# Input_v1_0.net
KiCad netlist of a schematic drawn in EAGLE
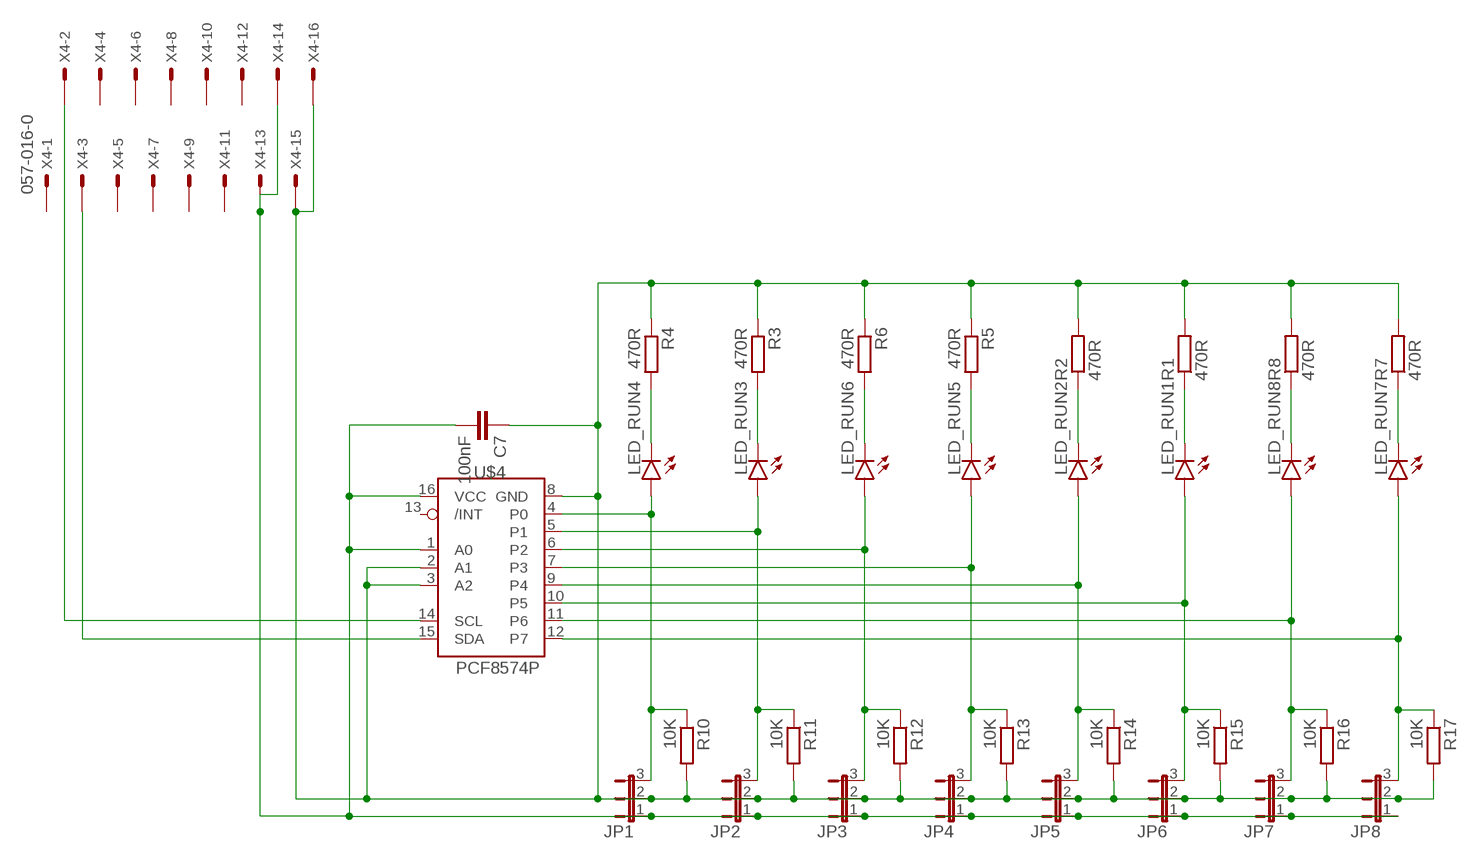
[diagram p0: schematic, sheet 1]

(export (version "E")
  (design (tool "Eeschema 10.0.6"))
  (components
    (comp (ref "C7")
      (value "100nF")
      (footprint "eagle-import:C025-024X044")
      (libsource (lib "eagle-import") (part "C-EU025-024X044"))
    )
    (comp (ref "JP1")
      (value "JP2E")
      (footprint "eagle-import:JP2")
      (libsource (lib "eagle-import") (part "JP2E"))
    )
    (comp (ref "JP2")
      (value "JP2E")
      (footprint "eagle-import:JP2")
      (libsource (lib "eagle-import") (part "JP2E"))
    )
    (comp (ref "JP3")
      (value "JP2E")
      (footprint "eagle-import:JP2")
      (libsource (lib "eagle-import") (part "JP2E"))
    )
    (comp (ref "JP4")
      (value "JP2E")
      (footprint "eagle-import:JP2")
      (libsource (lib "eagle-import") (part "JP2E"))
    )
    (comp (ref "JP5")
      (value "JP2E")
      (footprint "eagle-import:JP2")
      (libsource (lib "eagle-import") (part "JP2E"))
    )
    (comp (ref "JP6")
      (value "JP2E")
      (footprint "eagle-import:JP2")
      (libsource (lib "eagle-import") (part "JP2E"))
    )
    (comp (ref "JP7")
      (value "JP2E")
      (footprint "eagle-import:JP2")
      (libsource (lib "eagle-import") (part "JP2E"))
    )
    (comp (ref "JP8")
      (value "JP2E")
      (footprint "eagle-import:JP2")
      (libsource (lib "eagle-import") (part "JP2E"))
    )
    (comp (ref "LED_RUN1")
      (value "LED3MM")
      (footprint "eagle-import:LED3MM")
      (libsource (lib "eagle-import") (part "LED3MM"))
    )
    (comp (ref "LED_RUN2")
      (value "LED3MM")
      (footprint "eagle-import:LED3MM")
      (libsource (lib "eagle-import") (part "LED3MM"))
    )
    (comp (ref "LED_RUN3")
      (value "LED3MM")
      (footprint "eagle-import:LED3MM")
      (libsource (lib "eagle-import") (part "LED3MM"))
    )
    (comp (ref "LED_RUN4")
      (value "LED3MM")
      (footprint "eagle-import:LED3MM")
      (libsource (lib "eagle-import") (part "LED3MM"))
    )
    (comp (ref "LED_RUN5")
      (value "LED3MM")
      (footprint "eagle-import:LED3MM")
      (libsource (lib "eagle-import") (part "LED3MM"))
    )
    (comp (ref "LED_RUN6")
      (value "LED3MM")
      (footprint "eagle-import:LED3MM")
      (libsource (lib "eagle-import") (part "LED3MM"))
    )
    (comp (ref "LED_RUN7")
      (value "LED3MM")
      (footprint "eagle-import:LED3MM")
      (libsource (lib "eagle-import") (part "LED3MM"))
    )
    (comp (ref "LED_RUN8")
      (value "LED3MM")
      (footprint "eagle-import:LED3MM")
      (libsource (lib "eagle-import") (part "LED3MM"))
    )
    (comp (ref "R1")
      (value "470R")
      (footprint "eagle-import:0309_10")
      (libsource (lib "eagle-import") (part "R-EU_0309/10"))
    )
    (comp (ref "R2")
      (value "470R")
      (footprint "eagle-import:0309_10")
      (libsource (lib "eagle-import") (part "R-EU_0309/10"))
    )
    (comp (ref "R3")
      (value "470R")
      (footprint "eagle-import:0309_10")
      (libsource (lib "eagle-import") (part "R-EU_0309/10"))
    )
    (comp (ref "R4")
      (value "470R")
      (footprint "eagle-import:0309_10")
      (libsource (lib "eagle-import") (part "R-EU_0309/10"))
    )
    (comp (ref "R5")
      (value "470R")
      (footprint "eagle-import:0309_10")
      (libsource (lib "eagle-import") (part "R-EU_0309/10"))
    )
    (comp (ref "R6")
      (value "470R")
      (footprint "eagle-import:0309_10")
      (libsource (lib "eagle-import") (part "R-EU_0309/10"))
    )
    (comp (ref "R7")
      (value "470R")
      (footprint "eagle-import:0309_10")
      (libsource (lib "eagle-import") (part "R-EU_0309/10"))
    )
    (comp (ref "R8")
      (value "470R")
      (footprint "eagle-import:0309_10")
      (libsource (lib "eagle-import") (part "R-EU_0309/10"))
    )
    (comp (ref "R10")
      (value "10K")
      (footprint "eagle-import:0309_10")
      (libsource (lib "eagle-import") (part "R-EU_0309/10"))
    )
    (comp (ref "R11")
      (value "10K")
      (footprint "eagle-import:0309_10")
      (libsource (lib "eagle-import") (part "R-EU_0309/10"))
    )
    (comp (ref "R12")
      (value "10K")
      (footprint "eagle-import:0309_10")
      (libsource (lib "eagle-import") (part "R-EU_0309/10"))
    )
    (comp (ref "R13")
      (value "10K")
      (footprint "eagle-import:0309_10")
      (libsource (lib "eagle-import") (part "R-EU_0309/10"))
    )
    (comp (ref "R14")
      (value "10K")
      (footprint "eagle-import:0309_10")
      (libsource (lib "eagle-import") (part "R-EU_0309/10"))
    )
    (comp (ref "R15")
      (value "10K")
      (footprint "eagle-import:0309_10")
      (libsource (lib "eagle-import") (part "R-EU_0309/10"))
    )
    (comp (ref "R16")
      (value "10K")
      (footprint "eagle-import:0309_10")
      (libsource (lib "eagle-import") (part "R-EU_0309/10"))
    )
    (comp (ref "R17")
      (value "10K")
      (footprint "eagle-import:0309_10")
      (libsource (lib "eagle-import") (part "R-EU_0309/10"))
    )
    (comp (ref "U$4")
      (value "PCF8574P")
      (footprint "eagle-import:DIL16")
      (libsource (lib "eagle-import") (part "PCF8574P"))
    )
    (comp (ref "X4")
      (value "057-016-0")
      (footprint "eagle-import:057-016-0")
      (libsource (lib "eagle-import") (part "057-016-0"))
    )
  )
  (nets
    (net (code "1") (name "Net-(LED_RUN1-C)") (class "Default")
      (node (ref "LED_RUN1") (pin "K") (pinfunction "C_K") (pintype "passive"))
      (node (ref "R1") (pin "1") (pinfunction "1_1") (pintype "passive"))
    )
    (net (code "2") (name "Net-(LED_RUN2-C)") (class "Default")
      (node (ref "LED_RUN2") (pin "K") (pinfunction "C_K") (pintype "passive"))
      (node (ref "R2") (pin "1") (pinfunction "1_1") (pintype "passive"))
    )
    (net (code "3") (name "Net-(LED_RUN3-C)") (class "Default")
      (node (ref "LED_RUN3") (pin "K") (pinfunction "C_K") (pintype "passive"))
      (node (ref "R3") (pin "2") (pinfunction "2_2") (pintype "passive"))
    )
    (net (code "4") (name "Net-(LED_RUN4-C)") (class "Default")
      (node (ref "LED_RUN4") (pin "K") (pinfunction "C_K") (pintype "passive"))
      (node (ref "R4") (pin "2") (pinfunction "2_2") (pintype "passive"))
    )
    (net (code "5") (name "Net-(LED_RUN5-C)") (class "Default")
      (node (ref "LED_RUN5") (pin "K") (pinfunction "C_K") (pintype "passive"))
      (node (ref "R5") (pin "2") (pinfunction "2_2") (pintype "passive"))
    )
    (net (code "6") (name "Net-(LED_RUN6-C)") (class "Default")
      (node (ref "LED_RUN6") (pin "K") (pinfunction "C_K") (pintype "passive"))
      (node (ref "R6") (pin "2") (pinfunction "2_2") (pintype "passive"))
    )
    (net (code "7") (name "Net-(LED_RUN7-C)") (class "Default")
      (node (ref "LED_RUN7") (pin "K") (pinfunction "C_K") (pintype "passive"))
      (node (ref "R7") (pin "1") (pinfunction "1_1") (pintype "passive"))
    )
    (net (code "8") (name "Net-(LED_RUN8-C)") (class "Default")
      (node (ref "LED_RUN8") (pin "K") (pinfunction "C_K") (pintype "passive"))
      (node (ref "R8") (pin "1") (pinfunction "1_1") (pintype "passive"))
    )
    (net (code "9") (name "Net-(U$4-A0)") (class "Default")
      (node (ref "C7") (pin "2") (pinfunction "2_2") (pintype "passive"))
      (node (ref "JP1") (pin "1") (pinfunction "1_1") (pintype "passive"))
      (node (ref "JP2") (pin "1") (pinfunction "1_1") (pintype "passive"))
      (node (ref "JP3") (pin "1") (pinfunction "1_1") (pintype "passive"))
      (node (ref "JP4") (pin "1") (pinfunction "1_1") (pintype "passive"))
      (node (ref "JP5") (pin "1") (pinfunction "1_1") (pintype "passive"))
      (node (ref "JP6") (pin "1") (pinfunction "1_1") (pintype "passive"))
      (node (ref "JP7") (pin "1") (pinfunction "1_1") (pintype "passive"))
      (node (ref "JP8") (pin "1") (pinfunction "1_1") (pintype "passive"))
      (node (ref "U$4") (pin "1") (pinfunction "A0_1") (pintype "input"))
      (node (ref "U$4") (pin "16") (pinfunction "VCC_16") (pintype "power_in"))
      (node (ref "X4") (pin "13") (pinfunction "S_13") (pintype "passive"))
      (node (ref "X4") (pin "14") (pinfunction "S_14") (pintype "passive"))
    )
    (net (code "10") (name "Net-(U$4-A1)") (class "Default")
      (node (ref "C7") (pin "1") (pinfunction "1_1") (pintype "passive"))
      (node (ref "JP1") (pin "2") (pinfunction "2_2") (pintype "passive"))
      (node (ref "JP2") (pin "2") (pinfunction "2_2") (pintype "passive"))
      (node (ref "JP3") (pin "2") (pinfunction "2_2") (pintype "passive"))
      (node (ref "JP4") (pin "2") (pinfunction "2_2") (pintype "passive"))
      (node (ref "JP5") (pin "2") (pinfunction "2_2") (pintype "passive"))
      (node (ref "JP6") (pin "2") (pinfunction "2_2") (pintype "passive"))
      (node (ref "JP7") (pin "2") (pinfunction "2_2") (pintype "passive"))
      (node (ref "JP8") (pin "2") (pinfunction "2_2") (pintype "passive"))
      (node (ref "R1") (pin "2") (pinfunction "2_2") (pintype "passive"))
      (node (ref "R10") (pin "2") (pinfunction "2_2") (pintype "passive"))
      (node (ref "R11") (pin "2") (pinfunction "2_2") (pintype "passive"))
      (node (ref "R12") (pin "2") (pinfunction "2_2") (pintype "passive"))
      (node (ref "R13") (pin "2") (pinfunction "2_2") (pintype "passive"))
      (node (ref "R14") (pin "2") (pinfunction "2_2") (pintype "passive"))
      (node (ref "R15") (pin "2") (pinfunction "2_2") (pintype "passive"))
      (node (ref "R16") (pin "2") (pinfunction "2_2") (pintype "passive"))
      (node (ref "R17") (pin "2") (pinfunction "2_2") (pintype "passive"))
      (node (ref "R2") (pin "2") (pinfunction "2_2") (pintype "passive"))
      (node (ref "R3") (pin "1") (pinfunction "1_1") (pintype "passive"))
      (node (ref "R4") (pin "1") (pinfunction "1_1") (pintype "passive"))
      (node (ref "R5") (pin "1") (pinfunction "1_1") (pintype "passive"))
      (node (ref "R6") (pin "1") (pinfunction "1_1") (pintype "passive"))
      (node (ref "R7") (pin "2") (pinfunction "2_2") (pintype "passive"))
      (node (ref "R8") (pin "2") (pinfunction "2_2") (pintype "passive"))
      (node (ref "U$4") (pin "2") (pinfunction "A1_2") (pintype "input"))
      (node (ref "U$4") (pin "3") (pinfunction "A2_3") (pintype "input"))
      (node (ref "U$4") (pin "8") (pinfunction "GND_8") (pintype "power_in"))
      (node (ref "X4") (pin "15") (pinfunction "S_15") (pintype "passive"))
      (node (ref "X4") (pin "16") (pinfunction "S_16") (pintype "passive"))
    )
    (net (code "11") (name "Net-(U$4-P0)") (class "Default")
      (node (ref "JP1") (pin "3") (pinfunction "3_3") (pintype "passive"))
      (node (ref "LED_RUN4") (pin "A") (pinfunction "A_A") (pintype "passive"))
      (node (ref "R10") (pin "1") (pinfunction "1_1") (pintype "passive"))
      (node (ref "U$4") (pin "4") (pinfunction "P0_4") (pintype "bidirectional"))
    )
    (net (code "12") (name "Net-(U$4-P1)") (class "Default")
      (node (ref "JP2") (pin "3") (pinfunction "3_3") (pintype "passive"))
      (node (ref "LED_RUN3") (pin "A") (pinfunction "A_A") (pintype "passive"))
      (node (ref "R11") (pin "1") (pinfunction "1_1") (pintype "passive"))
      (node (ref "U$4") (pin "5") (pinfunction "P1_5") (pintype "bidirectional"))
    )
    (net (code "13") (name "Net-(U$4-P2)") (class "Default")
      (node (ref "JP3") (pin "3") (pinfunction "3_3") (pintype "passive"))
      (node (ref "LED_RUN6") (pin "A") (pinfunction "A_A") (pintype "passive"))
      (node (ref "R12") (pin "1") (pinfunction "1_1") (pintype "passive"))
      (node (ref "U$4") (pin "6") (pinfunction "P2_6") (pintype "bidirectional"))
    )
    (net (code "14") (name "Net-(U$4-P3)") (class "Default")
      (node (ref "JP4") (pin "3") (pinfunction "3_3") (pintype "passive"))
      (node (ref "LED_RUN5") (pin "A") (pinfunction "A_A") (pintype "passive"))
      (node (ref "R13") (pin "1") (pinfunction "1_1") (pintype "passive"))
      (node (ref "U$4") (pin "7") (pinfunction "P3_7") (pintype "bidirectional"))
    )
    (net (code "15") (name "Net-(U$4-P4)") (class "Default")
      (node (ref "JP5") (pin "3") (pinfunction "3_3") (pintype "passive"))
      (node (ref "LED_RUN2") (pin "A") (pinfunction "A_A") (pintype "passive"))
      (node (ref "R14") (pin "1") (pinfunction "1_1") (pintype "passive"))
      (node (ref "U$4") (pin "9") (pinfunction "P4_9") (pintype "bidirectional"))
    )
    (net (code "16") (name "Net-(U$4-P5)") (class "Default")
      (node (ref "JP6") (pin "3") (pinfunction "3_3") (pintype "passive"))
      (node (ref "LED_RUN1") (pin "A") (pinfunction "A_A") (pintype "passive"))
      (node (ref "R15") (pin "1") (pinfunction "1_1") (pintype "passive"))
      (node (ref "U$4") (pin "10") (pinfunction "P5_10") (pintype "bidirectional"))
    )
    (net (code "17") (name "Net-(U$4-P6)") (class "Default")
      (node (ref "JP7") (pin "3") (pinfunction "3_3") (pintype "passive"))
      (node (ref "LED_RUN8") (pin "A") (pinfunction "A_A") (pintype "passive"))
      (node (ref "R16") (pin "1") (pinfunction "1_1") (pintype "passive"))
      (node (ref "U$4") (pin "11") (pinfunction "P6_11") (pintype "bidirectional"))
    )
    (net (code "18") (name "Net-(U$4-P7)") (class "Default")
      (node (ref "JP8") (pin "3") (pinfunction "3_3") (pintype "passive"))
      (node (ref "LED_RUN7") (pin "A") (pinfunction "A_A") (pintype "passive"))
      (node (ref "R17") (pin "1") (pinfunction "1_1") (pintype "passive"))
      (node (ref "U$4") (pin "12") (pinfunction "P7_12") (pintype "bidirectional"))
    )
    (net (code "19") (name "Net-(U$4-SCL)") (class "Default")
      (node (ref "U$4") (pin "14") (pinfunction "SCL_14") (pintype "input"))
      (node (ref "X4") (pin "2") (pinfunction "S_2") (pintype "passive"))
    )
    (net (code "20") (name "Net-(U$4-SDA)") (class "Default")
      (node (ref "U$4") (pin "15") (pinfunction "SDA_15") (pintype "bidirectional"))
      (node (ref "X4") (pin "3") (pinfunction "S_3") (pintype "passive"))
    )
    (net (code "21") (name "unconnected-(U$4-{slash}INT-Pad13)") (class "Default")
      (node (ref "U$4") (pin "13") (pinfunction "/INT_13") (pintype "output"))
    )
    (net (code "22") (name "unconnected-(X4A-S-Pad1)") (class "Default")
      (node (ref "X4") (pin "1") (pinfunction "S_1") (pintype "passive"))
    )
    (net (code "23") (name "unconnected-(X4B-S-Pad10)") (class "Default")
      (node (ref "X4") (pin "10") (pinfunction "S_10") (pintype "passive"))
    )
    (net (code "24") (name "unconnected-(X4C-S-Pad11)") (class "Default")
      (node (ref "X4") (pin "11") (pinfunction "S_11") (pintype "passive"))
    )
    (net (code "25") (name "unconnected-(X4D-S-Pad12)") (class "Default")
      (node (ref "X4") (pin "12") (pinfunction "S_12") (pintype "passive"))
    )
    (net (code "26") (name "unconnected-(X4K-S-Pad4)") (class "Default")
      (node (ref "X4") (pin "4") (pinfunction "S_4") (pintype "passive"))
    )
    (net (code "27") (name "unconnected-(X4L-S-Pad5)") (class "Default")
      (node (ref "X4") (pin "5") (pinfunction "S_5") (pintype "passive"))
    )
    (net (code "28") (name "unconnected-(X4M-S-Pad6)") (class "Default")
      (node (ref "X4") (pin "6") (pinfunction "S_6") (pintype "passive"))
    )
    (net (code "29") (name "unconnected-(X4N-S-Pad7)") (class "Default")
      (node (ref "X4") (pin "7") (pinfunction "S_7") (pintype "passive"))
    )
    (net (code "30") (name "unconnected-(X4O-S-Pad8)") (class "Default")
      (node (ref "X4") (pin "8") (pinfunction "S_8") (pintype "passive"))
    )
    (net (code "31") (name "unconnected-(X4P-S-Pad9)") (class "Default")
      (node (ref "X4") (pin "9") (pinfunction "S_9") (pintype "passive"))
    )
  )
)
